# Black-CP2102-Zigbee-SMD-V001-not-produce.net
KiCad netlist of a schematic drawn in EAGLE
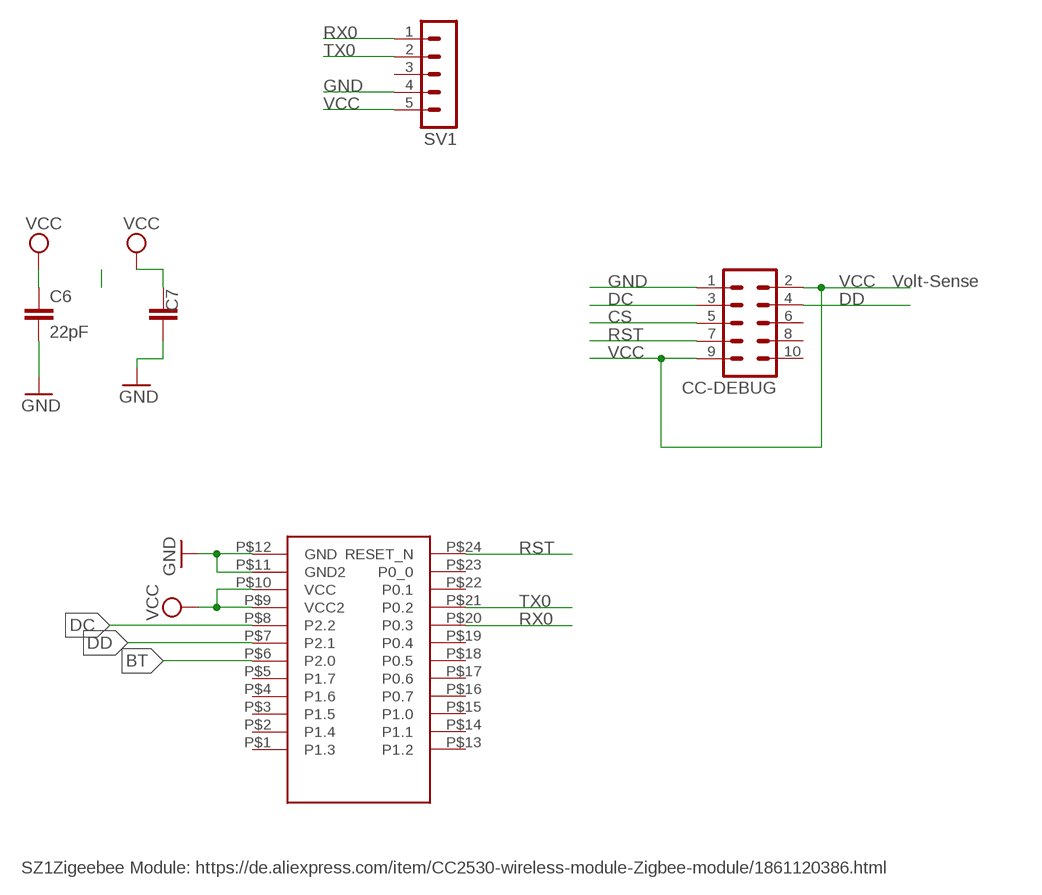
[diagram p0: schematic, sheet 1]

(export (version "E")
  (design (tool "Eeschema 10.0.6"))
  (components
    (comp (ref "C6")
      (value "22pF")
      (footprint "eagle-import:C0805")
      (libsource (lib "eagle-import") (part "C-EUC0805"))
    )
    (comp (ref "C7")
      (value "C-EUC1812")
      (footprint "eagle-import:C1812")
      (libsource (lib "eagle-import") (part "C-EUC1812"))
    )
    (comp (ref "CC-DEBUG")
      (value "MA05-2")
      (footprint "eagle-import:MA05-2")
      (libsource (lib "eagle-import") (part "MA05-2"))
    )
    (comp (ref "SV1")
      (value "MA05-1")
      (footprint "eagle-import:MA05-1")
      (libsource (lib "eagle-import") (part "MA05-1"))
    )
    (comp (ref "U$1")
      (value "CC2530")
      (footprint "eagle-import:SZ1ZIGBEE-SMD")
      (libsource (lib "eagle-import") (part "CC2530"))
    )
  )
  (nets
    (net (code "1") (name "/CS") (class "Default")
      (node (ref "CC-DEBUG") (pin "5") (pinfunction "5_5") (pintype "passive"))
    )
    (net (code "2") (name "/RST") (class "Default")
      (node (ref "CC-DEBUG") (pin "7") (pinfunction "7_7") (pintype "passive"))
      (node (ref "U$1") (pin "P$24") (pinfunction "RESET_N_P$24") (pintype "bidirectional"))
    )
    (net (code "3") (name "/RX0") (class "Default")
      (node (ref "SV1") (pin "1") (pinfunction "1_1") (pintype "passive"))
      (node (ref "U$1") (pin "P$20") (pinfunction "P0.3_P$20") (pintype "bidirectional"))
    )
    (net (code "4") (name "/TX0") (class "Default")
      (node (ref "SV1") (pin "2") (pinfunction "2_2") (pintype "passive"))
      (node (ref "U$1") (pin "P$21") (pinfunction "P0.2_P$21") (pintype "bidirectional"))
    )
    (net (code "5") (name "BT") (class "Default")
      (node (ref "U$1") (pin "P$6") (pinfunction "P2.0_P$6") (pintype "bidirectional"))
    )
    (net (code "6") (name "DC") (class "Default")
      (node (ref "CC-DEBUG") (pin "3") (pinfunction "3_3") (pintype "passive"))
      (node (ref "U$1") (pin "P$8") (pinfunction "P2.2_P$8") (pintype "bidirectional"))
    )
    (net (code "7") (name "DD") (class "Default")
      (node (ref "CC-DEBUG") (pin "4") (pinfunction "4_4") (pintype "passive"))
      (node (ref "U$1") (pin "P$7") (pinfunction "P2.1_P$7") (pintype "bidirectional"))
    )
    (net (code "8") (name "GND") (class "Default")
      (node (ref "C6") (pin "2") (pinfunction "2_2") (pintype "passive"))
      (node (ref "C7") (pin "1") (pinfunction "1_1") (pintype "passive"))
      (node (ref "CC-DEBUG") (pin "1") (pinfunction "1_1") (pintype "passive"))
      (node (ref "SV1") (pin "4") (pinfunction "4_4") (pintype "passive"))
      (node (ref "U$1") (pin "P$11") (pinfunction "GND2_P$11") (pintype "bidirectional"))
      (node (ref "U$1") (pin "P$12") (pinfunction "GND_P$12") (pintype "bidirectional"))
    )
    (net (code "9") (name "VCC") (class "Default")
      (node (ref "C6") (pin "1") (pinfunction "1_1") (pintype "passive"))
      (node (ref "C7") (pin "2") (pinfunction "2_2") (pintype "passive"))
      (node (ref "CC-DEBUG") (pin "2") (pinfunction "2_2") (pintype "passive"))
      (node (ref "CC-DEBUG") (pin "9") (pinfunction "9_9") (pintype "passive"))
      (node (ref "SV1") (pin "5") (pinfunction "5_5") (pintype "passive"))
      (node (ref "U$1") (pin "P$10") (pinfunction "VCC_P$10") (pintype "bidirectional"))
      (node (ref "U$1") (pin "P$9") (pinfunction "VCC2_P$9") (pintype "bidirectional"))
    )
    (net (code "10") (name "unconnected-(CC-DEBUG-Pad6)") (class "Default")
      (node (ref "CC-DEBUG") (pin "6") (pinfunction "6_6") (pintype "passive"))
    )
    (net (code "11") (name "unconnected-(CC-DEBUG-Pad8)") (class "Default")
      (node (ref "CC-DEBUG") (pin "8") (pinfunction "8_8") (pintype "passive"))
    )
    (net (code "12") (name "unconnected-(CC-DEBUG-Pad10)") (class "Default")
      (node (ref "CC-DEBUG") (pin "10") (pinfunction "10_10") (pintype "passive"))
    )
    (net (code "13") (name "unconnected-(SV1-Pad3)") (class "Default")
      (node (ref "SV1") (pin "3") (pinfunction "3_3") (pintype "passive"))
    )
    (net (code "14") (name "unconnected-(U$1-P0.1-PadP$22)") (class "Default")
      (node (ref "U$1") (pin "P$22") (pinfunction "P0.1_P$22") (pintype "bidirectional"))
    )
    (net (code "15") (name "unconnected-(U$1-P0.4-PadP$19)") (class "Default")
      (node (ref "U$1") (pin "P$19") (pinfunction "P0.4_P$19") (pintype "bidirectional"))
    )
    (net (code "16") (name "unconnected-(U$1-P0.5-PadP$18)") (class "Default")
      (node (ref "U$1") (pin "P$18") (pinfunction "P0.5_P$18") (pintype "bidirectional"))
    )
    (net (code "17") (name "unconnected-(U$1-P0.6-PadP$17)") (class "Default")
      (node (ref "U$1") (pin "P$17") (pinfunction "P0.6_P$17") (pintype "bidirectional"))
    )
    (net (code "18") (name "unconnected-(U$1-P0.7-PadP$16)") (class "Default")
      (node (ref "U$1") (pin "P$16") (pinfunction "P0.7_P$16") (pintype "bidirectional"))
    )
    (net (code "19") (name "unconnected-(U$1-P0_0-PadP$23)") (class "Default")
      (node (ref "U$1") (pin "P$23") (pinfunction "P0_0_P$23") (pintype "bidirectional"))
    )
    (net (code "20") (name "unconnected-(U$1-P1.0-PadP$15)") (class "Default")
      (node (ref "U$1") (pin "P$15") (pinfunction "P1.0_P$15") (pintype "bidirectional"))
    )
    (net (code "21") (name "unconnected-(U$1-P1.1-PadP$14)") (class "Default")
      (node (ref "U$1") (pin "P$14") (pinfunction "P1.1_P$14") (pintype "bidirectional"))
    )
    (net (code "22") (name "unconnected-(U$1-P1.2-PadP$13)") (class "Default")
      (node (ref "U$1") (pin "P$13") (pinfunction "P1.2_P$13") (pintype "bidirectional"))
    )
    (net (code "23") (name "unconnected-(U$1-P1.3-PadP$1)") (class "Default")
      (node (ref "U$1") (pin "P$1") (pinfunction "P1.3_P$1") (pintype "bidirectional"))
    )
    (net (code "24") (name "unconnected-(U$1-P1.4-PadP$2)") (class "Default")
      (node (ref "U$1") (pin "P$2") (pinfunction "P1.4_P$2") (pintype "bidirectional"))
    )
    (net (code "25") (name "unconnected-(U$1-P1.5-PadP$3)") (class "Default")
      (node (ref "U$1") (pin "P$3") (pinfunction "P1.5_P$3") (pintype "bidirectional"))
    )
    (net (code "26") (name "unconnected-(U$1-P1.6-PadP$4)") (class "Default")
      (node (ref "U$1") (pin "P$4") (pinfunction "P1.6_P$4") (pintype "bidirectional"))
    )
    (net (code "27") (name "unconnected-(U$1-P1.7-PadP$5)") (class "Default")
      (node (ref "U$1") (pin "P$5") (pinfunction "P1.7_P$5") (pintype "bidirectional"))
    )
  )
)
